# follower_2013-3.net
KiCad netlist of a schematic drawn in EAGLE
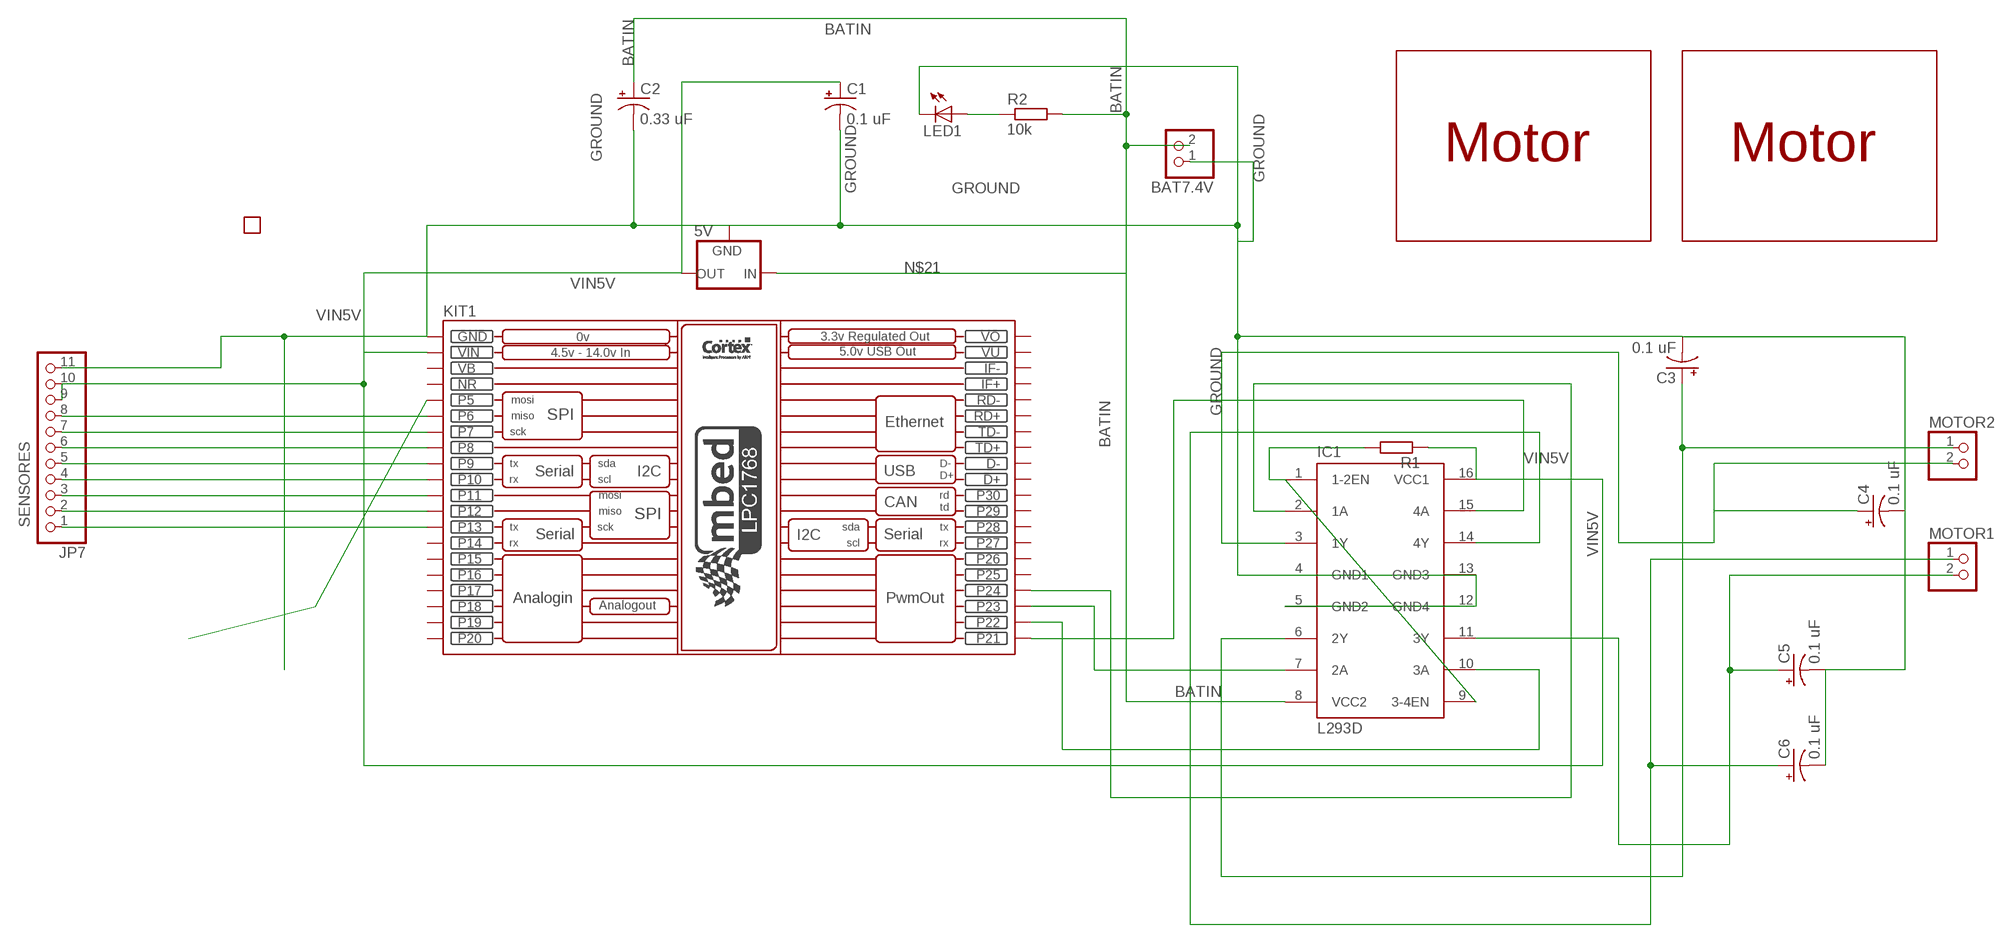
[diagram p0: schematic, sheet 1]

(export (version "E")
  (design (tool "Eeschema 10.0.6"))
  (components
    (comp (ref "5V")
      (value "78XXL")
      (footprint "eagle-import:78XXL")
      (libsource (lib "eagle-import") (part "78XXL"))
    )
    (comp (ref "BAT7.4V")
      (value "PINHD-1X2")
      (footprint "eagle-import:1X02")
      (libsource (lib "eagle-import") (part "PINHD-1X2"))
    )
    (comp (ref "C1")
      (value "0.1 uF")
      (footprint "eagle-import:TT5D6")
      (libsource (lib "eagle-import") (part "CPOL-USTT6D6"))
    )
    (comp (ref "C2")
      (value "0.33 uF")
      (footprint "eagle-import:TT5D6")
      (libsource (lib "eagle-import") (part "CPOL-USTT6D6"))
    )
    (comp (ref "C3")
      (value "0.1 uF")
      (footprint "eagle-import:TT5D6")
      (libsource (lib "eagle-import") (part "CPOL-USTT6D6"))
    )
    (comp (ref "C4")
      (value "0.1 uF")
      (footprint "eagle-import:TT5D6")
      (libsource (lib "eagle-import") (part "CPOL-USTT6D6"))
    )
    (comp (ref "C5")
      (value "0.1 uF")
      (footprint "eagle-import:TT5D6")
      (libsource (lib "eagle-import") (part "CPOL-USTT6D6"))
    )
    (comp (ref "C6")
      (value "0.1 uF")
      (footprint "eagle-import:TT5D6")
      (libsource (lib "eagle-import") (part "CPOL-USTT6D6"))
    )
    (comp (ref "IC1")
      (value "L293D")
      (footprint "eagle-import:DIL16")
      (libsource (lib "eagle-import") (part "L293D"))
    )
    (comp (ref "JP7")
      (value "PINHD-1X11")
      (footprint "eagle-import:1X11")
      (libsource (lib "eagle-import") (part "PINHD-1X11"))
    )
    (comp (ref "KIT1")
      (value "MBED_NXP_LPC1768")
      (footprint "eagle-import:MBED-KIT")
      (libsource (lib "eagle-import") (part "MBED_NXP_LPC1768"))
    )
    (comp (ref "LED1")
      (value "LED3MM")
      (footprint "eagle-import:LED3MM")
      (libsource (lib "eagle-import") (part "LED3MM"))
    )
    (comp (ref "MOTOR1")
      (value "PINHD-1X2")
      (footprint "eagle-import:1X02")
      (libsource (lib "eagle-import") (part "PINHD-1X2"))
    )
    (comp (ref "MOTOR2")
      (value "PINHD-1X2")
      (footprint "eagle-import:1X02")
      (libsource (lib "eagle-import") (part "PINHD-1X2"))
    )
    (comp (ref "R1")
      (value "R-EU_0204/2V")
      (footprint "eagle-import:0204V")
      (libsource (lib "eagle-import") (part "R-EU_0204/2V"))
    )
    (comp (ref "R2")
      (value "10k")
      (footprint "eagle-import:0204_5")
      (libsource (lib "eagle-import") (part "R-EU_0204/5"))
    )
    (comp (ref "U$1")
      (value "BATERIA7.4V")
      (footprint "eagle-import:BATERIA7.4V")
      (libsource (lib "eagle-import") (part "BATERIA7.4V"))
    )
    (comp (ref "U$2")
      (value "MOTOR")
      (footprint "eagle-import:MOTOR")
      (libsource (lib "eagle-import") (part "MOTOR"))
    )
    (comp (ref "U$3")
      (value "MOTOR")
      (footprint "eagle-import:MOTOR")
      (libsource (lib "eagle-import") (part "MOTOR"))
    )
  )
  (nets
    (net (code "1") (name "/BATIN") (class "Default")
      (node (ref "BAT7.4V") (pin "2") (pinfunction "2_2") (pintype "passive"))
      (node (ref "C2") (pin "+") (pinfunction "+_+") (pintype "passive"))
      (node (ref "IC1") (pin "8") (pinfunction "VCC2_8") (pintype "power_in"))
      (node (ref "R2") (pin "2") (pinfunction "2_2") (pintype "passive"))
    )
    (net (code "2") (name "/GROUND") (class "Default")
      (node (ref "5V") (pin "GND") (pinfunction "GND_GND") (pintype "input"))
      (node (ref "BAT7.4V") (pin "1") (pinfunction "1_1") (pintype "passive"))
      (node (ref "C1") (pin "-") (pinfunction "-_-") (pintype "passive"))
      (node (ref "C2") (pin "-") (pinfunction "-_-") (pintype "passive"))
      (node (ref "C3") (pin "-") (pinfunction "-_-") (pintype "passive"))
      (node (ref "C4") (pin "-") (pinfunction "-_-") (pintype "passive"))
      (node (ref "C5") (pin "-") (pinfunction "-_-") (pintype "passive"))
      (node (ref "C6") (pin "-") (pinfunction "-_-") (pintype "passive"))
      (node (ref "IC1") (pin "12") (pinfunction "GND4_12") (pintype "power_in"))
      (node (ref "IC1") (pin "13") (pinfunction "GND3_13") (pintype "power_in"))
      (node (ref "IC1") (pin "4") (pinfunction "GND1_4") (pintype "power_in"))
      (node (ref "IC1") (pin "5") (pinfunction "GND2_5") (pintype "power_in"))
      (node (ref "JP7") (pin "11") (pinfunction "S8_11") (pintype "passive"))
      (node (ref "KIT1") (pin "GND") (pinfunction "GND_GND") (pintype "power_in"))
      (node (ref "LED1") (pin "K") (pinfunction "C_K") (pintype "passive"))
    )
    (net (code "3") (name "/N$21") (class "Default")
      (node (ref "5V") (pin "IN") (pinfunction "IN_IN") (pintype "input"))
    )
    (net (code "4") (name "/NR") (class "Default")
      (node (ref "KIT1") (pin "NR") (pinfunction "NR_NR") (pintype "power_in"))
    )
    (net (code "5") (name "/SENSORES") (class "Default")
      (node (ref "JP7") (pin "1") (pinfunction "GND_1") (pintype "passive"))
      (node (ref "KIT1") (pin "P$13") (pinfunction "P13_P$13") (pintype "bidirectional"))
    )
    (net (code "6") (name "/VB") (class "Default")
      (node (ref "KIT1") (pin "VB") (pinfunction "VB_VB") (pintype "power_in"))
    )
    (net (code "7") (name "/VIN5V") (class "Default")
      (node (ref "5V") (pin "OUT") (pinfunction "OUT_OUT") (pintype "passive"))
      (node (ref "C1") (pin "+") (pinfunction "+_+") (pintype "passive"))
      (node (ref "IC1") (pin "16") (pinfunction "VCC1_16") (pintype "power_in"))
      (node (ref "JP7") (pin "10") (pinfunction "S7_10") (pintype "passive"))
      (node (ref "JP7") (pin "9") (pinfunction "S6_9") (pintype "passive"))
      (node (ref "KIT1") (pin "VIN") (pinfunction "VIN_VIN") (pintype "power_in"))
      (node (ref "R1") (pin "1") (pinfunction "1_1") (pintype "passive"))
    )
    (net (code "8") (name "/VO") (class "Default")
      (node (ref "KIT1") (pin "VOUT") (pinfunction "VO_VOUT") (pintype "power_in"))
    )
    (net (code "9") (name "/VU") (class "Default")
      (node (ref "KIT1") (pin "VU") (pinfunction "VU_VU") (pintype "power_in"))
    )
    (net (code "10") (name "Net-(IC1-1-2EN)") (class "Default")
      (node (ref "IC1") (pin "1") (pinfunction "1-2EN_1") (pintype "input"))
      (node (ref "IC1") (pin "9") (pinfunction "3-4EN_9") (pintype "input"))
      (node (ref "R1") (pin "2") (pinfunction "2_2") (pintype "passive"))
    )
    (net (code "11") (name "Net-(IC1-1A)") (class "Default")
      (node (ref "IC1") (pin "2") (pinfunction "1A_2") (pintype "input"))
      (node (ref "KIT1") (pin "P$24") (pinfunction "P24_P$24") (pintype "bidirectional"))
    )
    (net (code "12") (name "Net-(IC1-1Y)") (class "Default")
      (node (ref "C4") (pin "+") (pinfunction "+_+") (pintype "passive"))
      (node (ref "IC1") (pin "3") (pinfunction "1Y_3") (pintype "output"))
      (node (ref "MOTOR2") (pin "2") (pinfunction "2_2") (pintype "passive"))
    )
    (net (code "13") (name "Net-(IC1-2A)") (class "Default")
      (node (ref "IC1") (pin "7") (pinfunction "2A_7") (pintype "input"))
      (node (ref "KIT1") (pin "P$23") (pinfunction "P23_P$23") (pintype "bidirectional"))
    )
    (net (code "14") (name "Net-(IC1-2Y)") (class "Default")
      (node (ref "C3") (pin "+") (pinfunction "+_+") (pintype "passive"))
      (node (ref "IC1") (pin "6") (pinfunction "2Y_6") (pintype "output"))
      (node (ref "MOTOR2") (pin "1") (pinfunction "1_1") (pintype "passive"))
    )
    (net (code "15") (name "Net-(IC1-3A)") (class "Default")
      (node (ref "IC1") (pin "10") (pinfunction "3A_10") (pintype "input"))
      (node (ref "KIT1") (pin "P$22") (pinfunction "P22_P$22") (pintype "bidirectional"))
    )
    (net (code "16") (name "Net-(IC1-3Y)") (class "Default")
      (node (ref "C5") (pin "+") (pinfunction "+_+") (pintype "passive"))
      (node (ref "IC1") (pin "11") (pinfunction "3Y_11") (pintype "output"))
      (node (ref "MOTOR1") (pin "2") (pinfunction "2_2") (pintype "passive"))
    )
    (net (code "17") (name "Net-(IC1-4A)") (class "Default")
      (node (ref "IC1") (pin "15") (pinfunction "4A_15") (pintype "input"))
      (node (ref "KIT1") (pin "P$21") (pinfunction "P21_P$21") (pintype "bidirectional"))
    )
    (net (code "18") (name "Net-(IC1-4Y)") (class "Default")
      (node (ref "C6") (pin "+") (pinfunction "+_+") (pintype "passive"))
      (node (ref "IC1") (pin "14") (pinfunction "4Y_14") (pintype "output"))
      (node (ref "MOTOR1") (pin "1") (pinfunction "1_1") (pintype "passive"))
    )
    (net (code "19") (name "Net-(JP7-S1)") (class "Default")
      (node (ref "JP7") (pin "4") (pinfunction "S1_4") (pintype "passive"))
      (node (ref "KIT1") (pin "P$10") (pinfunction "P10_P$10") (pintype "bidirectional"))
    )
    (net (code "20") (name "Net-(JP7-S2)") (class "Default")
      (node (ref "JP7") (pin "5") (pinfunction "S2_5") (pintype "passive"))
      (node (ref "KIT1") (pin "P$9") (pinfunction "P9_P$9") (pintype "bidirectional"))
    )
    (net (code "21") (name "Net-(JP7-S3)") (class "Default")
      (node (ref "JP7") (pin "6") (pinfunction "S3_6") (pintype "passive"))
      (node (ref "KIT1") (pin "P$8") (pinfunction "P8_P$8") (pintype "bidirectional"))
    )
    (net (code "22") (name "Net-(JP7-S4)") (class "Default")
      (node (ref "JP7") (pin "7") (pinfunction "S4_7") (pintype "passive"))
      (node (ref "KIT1") (pin "P$7") (pinfunction "P7_P$7") (pintype "bidirectional"))
    )
    (net (code "23") (name "Net-(JP7-S5)") (class "Default")
      (node (ref "JP7") (pin "8") (pinfunction "S5_8") (pintype "passive"))
      (node (ref "KIT1") (pin "P$6") (pinfunction "P6_P$6") (pintype "bidirectional"))
    )
    (net (code "24") (name "Net-(JP7-VCC)") (class "Default")
      (node (ref "JP7") (pin "2") (pinfunction "VCC_2") (pintype "passive"))
      (node (ref "KIT1") (pin "P$12") (pinfunction "P12_P$12") (pintype "bidirectional"))
    )
    (net (code "25") (name "Net-(JP7-VCCLED)") (class "Default")
      (node (ref "JP7") (pin "3") (pinfunction "VCCLED_3") (pintype "passive"))
      (node (ref "KIT1") (pin "P$11") (pinfunction "P11_P$11") (pintype "bidirectional"))
    )
    (net (code "26") (name "Net-(LED1-PadA)") (class "Default")
      (node (ref "LED1") (pin "A") (pinfunction "A_A") (pintype "passive"))
      (node (ref "R2") (pin "1") (pinfunction "1_1") (pintype "passive"))
    )
    (net (code "27") (name "unconnected-(KIT1-P5-PadP$5)") (class "Default")
      (node (ref "KIT1") (pin "P$5") (pinfunction "P5_P$5") (pintype "bidirectional"))
    )
    (net (code "28") (name "unconnected-(KIT1-P14-PadP$14)") (class "Default")
      (node (ref "KIT1") (pin "P$14") (pinfunction "P14_P$14") (pintype "bidirectional"))
    )
    (net (code "29") (name "unconnected-(KIT1-P15-PadP$15)") (class "Default")
      (node (ref "KIT1") (pin "P$15") (pinfunction "P15_P$15") (pintype "bidirectional"))
    )
    (net (code "30") (name "unconnected-(KIT1-P16-PadP$16)") (class "Default")
      (node (ref "KIT1") (pin "P$16") (pinfunction "P16_P$16") (pintype "bidirectional"))
    )
    (net (code "31") (name "unconnected-(KIT1-P17-PadP$17)") (class "Default")
      (node (ref "KIT1") (pin "P$17") (pinfunction "P17_P$17") (pintype "bidirectional"))
    )
    (net (code "32") (name "unconnected-(KIT1-P18-PadP$18)") (class "Default")
      (node (ref "KIT1") (pin "P$18") (pinfunction "P18_P$18") (pintype "bidirectional"))
    )
    (net (code "33") (name "unconnected-(KIT1-P19-PadP$19)") (class "Default")
      (node (ref "KIT1") (pin "P$19") (pinfunction "P19_P$19") (pintype "bidirectional"))
    )
    (net (code "34") (name "unconnected-(KIT1-P20-PadP$20)") (class "Default")
      (node (ref "KIT1") (pin "P$20") (pinfunction "P20_P$20") (pintype "bidirectional"))
    )
    (net (code "35") (name "unconnected-(KIT1-P25-PadP$25)") (class "Default")
      (node (ref "KIT1") (pin "P$25") (pinfunction "P25_P$25") (pintype "bidirectional"))
    )
    (net (code "36") (name "unconnected-(KIT1-P26-PadP$26)") (class "Default")
      (node (ref "KIT1") (pin "P$26") (pinfunction "P26_P$26") (pintype "bidirectional"))
    )
    (net (code "37") (name "unconnected-(KIT1-P27-PadP$27)") (class "Default")
      (node (ref "KIT1") (pin "P$27") (pinfunction "P27_P$27") (pintype "bidirectional"))
    )
    (net (code "38") (name "unconnected-(KIT1-P28-PadP$28)") (class "Default")
      (node (ref "KIT1") (pin "P$28") (pinfunction "P28_P$28") (pintype "bidirectional"))
    )
    (net (code "39") (name "unconnected-(KIT1-P29-PadP$29)") (class "Default")
      (node (ref "KIT1") (pin "P$29") (pinfunction "P29_P$29") (pintype "bidirectional"))
    )
    (net (code "40") (name "unconnected-(KIT1-P30-PadP$30)") (class "Default")
      (node (ref "KIT1") (pin "P$30") (pinfunction "P30_P$30") (pintype "bidirectional"))
    )
    (net (code "41") (name "unconnected-(KIT1-PadD+)") (class "Default")
      (node (ref "KIT1") (pin "D+") (pinfunction "D+_D+") (pintype "bidirectional"))
    )
    (net (code "42") (name "unconnected-(KIT1-PadD-)") (class "Default")
      (node (ref "KIT1") (pin "D-") (pinfunction "D-_D-") (pintype "bidirectional"))
    )
    (net (code "43") (name "unconnected-(KIT1-PadIF+)") (class "Default")
      (node (ref "KIT1") (pin "IF+") (pinfunction "IF+_IF+") (pintype "bidirectional"))
    )
    (net (code "44") (name "unconnected-(KIT1-PadIF-)") (class "Default")
      (node (ref "KIT1") (pin "IF-") (pinfunction "IF-_IF-") (pintype "bidirectional"))
    )
    (net (code "45") (name "unconnected-(KIT1-PadRD+)") (class "Default")
      (node (ref "KIT1") (pin "RD+") (pinfunction "RD+_RD+") (pintype "bidirectional"))
    )
    (net (code "46") (name "unconnected-(KIT1-PadRD-)") (class "Default")
      (node (ref "KIT1") (pin "RD-") (pinfunction "RD-_RD-") (pintype "bidirectional"))
    )
    (net (code "47") (name "unconnected-(KIT1-PadTD+)") (class "Default")
      (node (ref "KIT1") (pin "TD+") (pinfunction "TD+_TD+") (pintype "bidirectional"))
    )
    (net (code "48") (name "unconnected-(KIT1-PadTD-)") (class "Default")
      (node (ref "KIT1") (pin "TD-") (pinfunction "TD-_TD-") (pintype "bidirectional"))
    )
  )
)
